# sheet1.net
KiCad netlist of a schematic drawn in Altium Designer
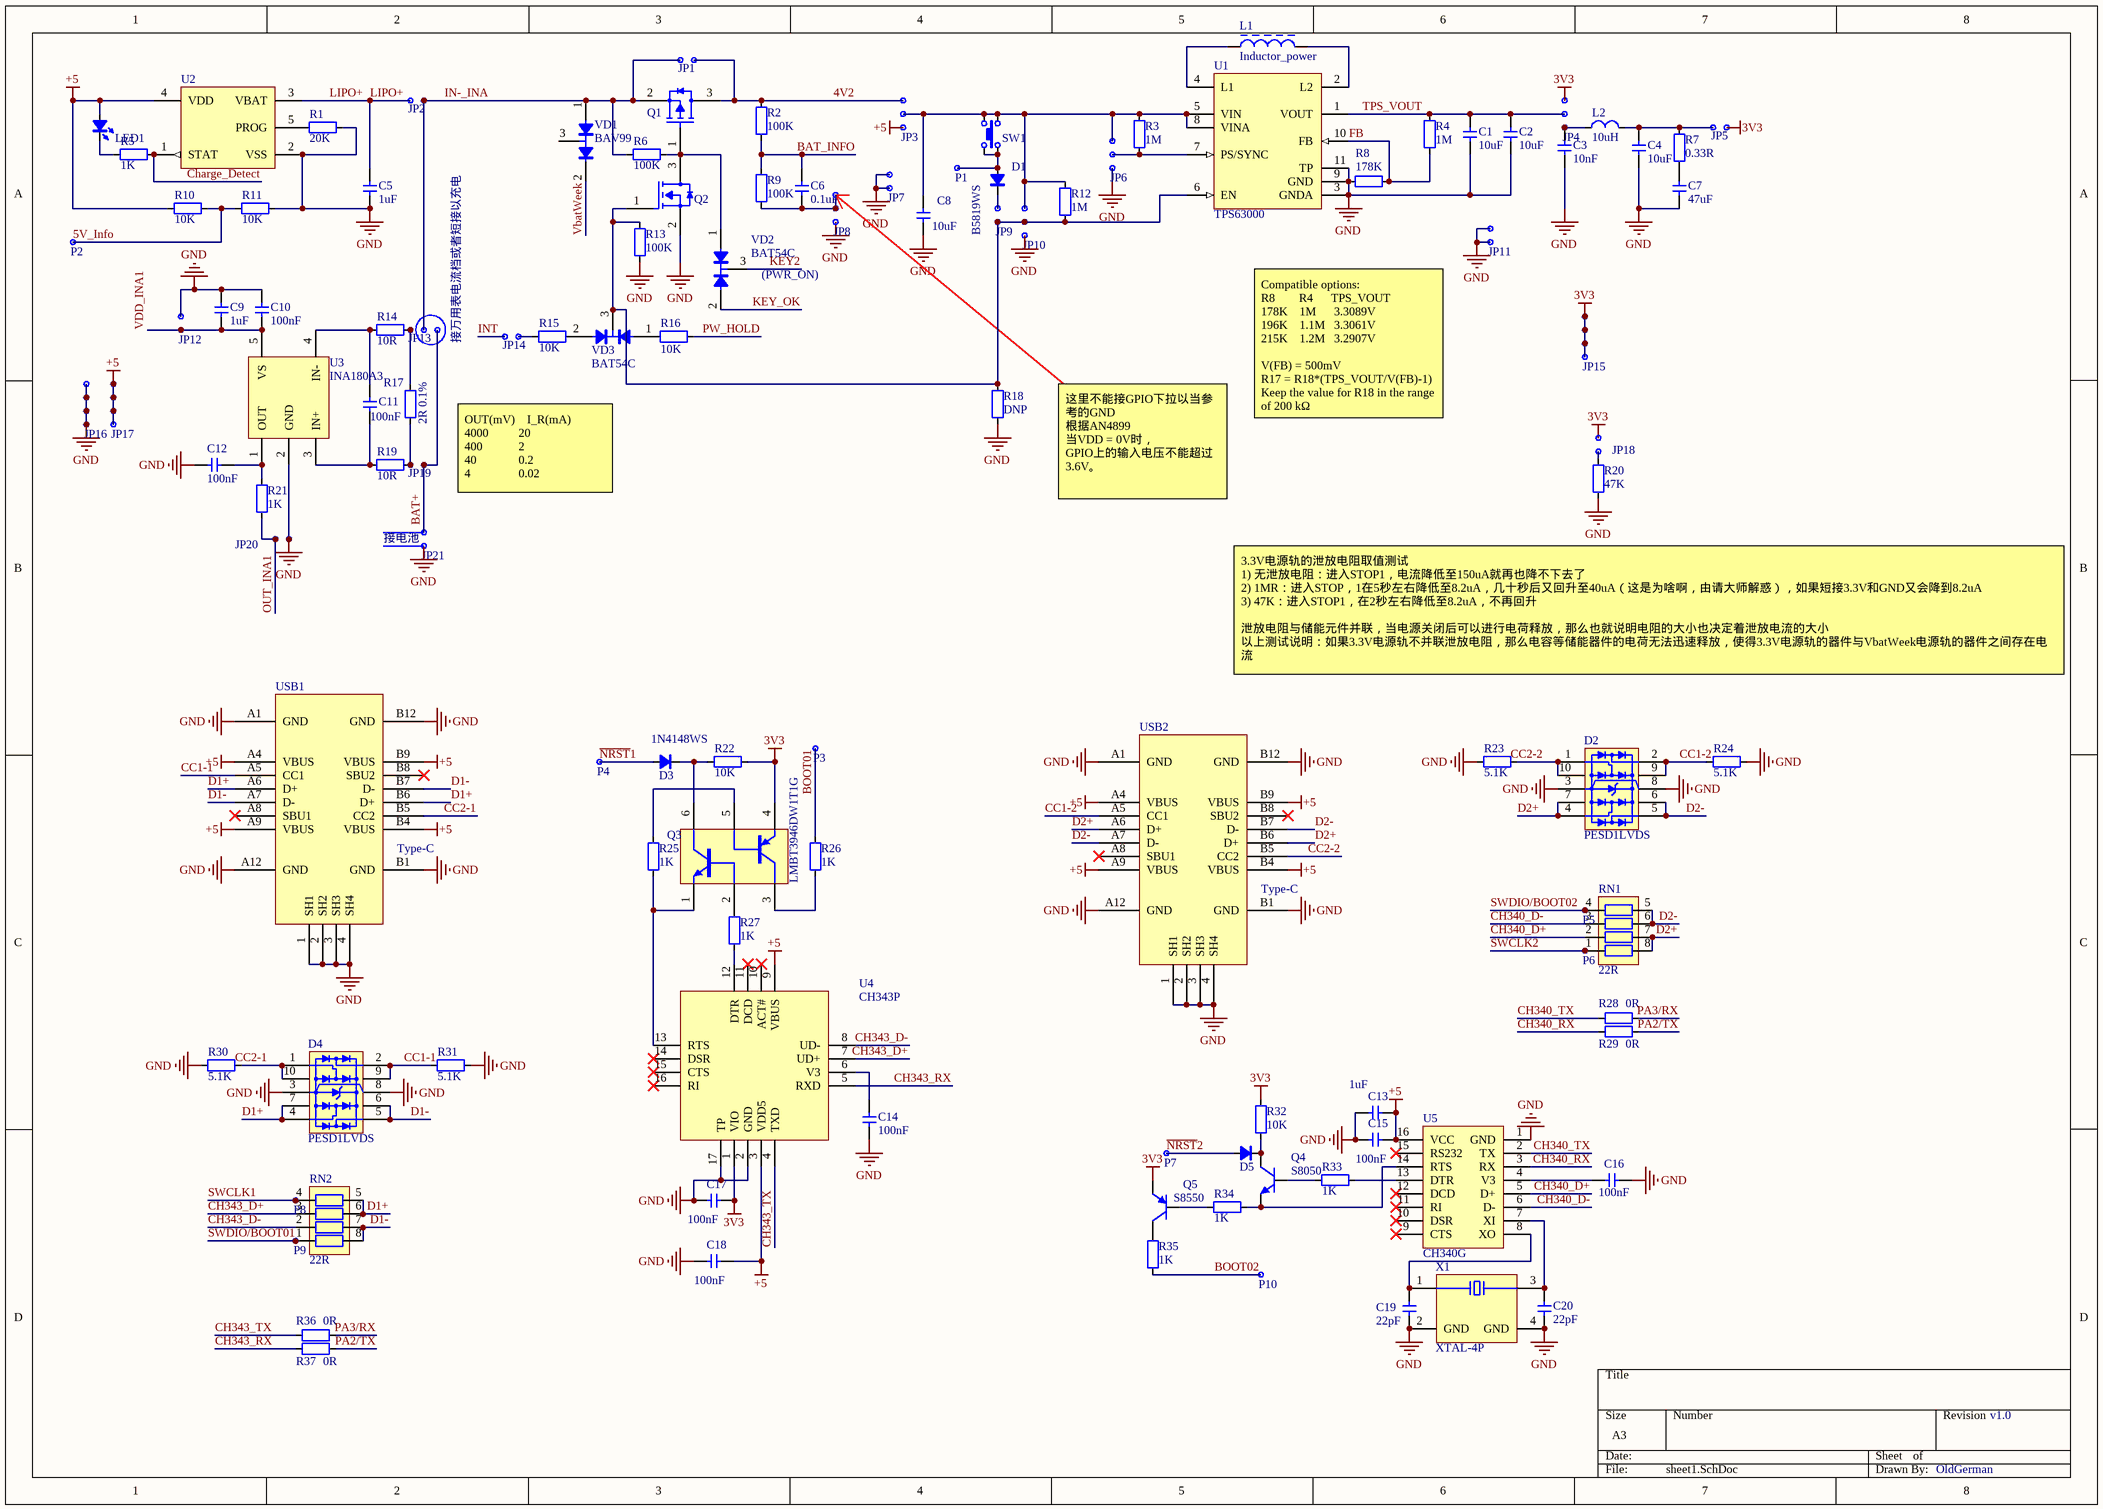
[diagram p0: sheet1.SchDoc]

(export (version "E")
  (design (tool "Eeschema 10.0.6"))
  (components
    (comp (ref "C1")
      (value "10uF")
      (footprint "C0603")
      (description "Capacitor")
      (libsource (lib "ODG_AD_Lib") (part "CAP"))
    )
    (comp (ref "C2")
      (value "10uF")
      (footprint "C0603")
      (description "Capacitor")
      (libsource (lib "ODG_AD_Lib") (part "CAP"))
    )
    (comp (ref "C3")
      (value "10nF")
      (footprint "C0603")
      (description "Capacitor")
      (libsource (lib "ODG_AD_Lib") (part "CAP"))
    )
    (comp (ref "C4")
      (value "10uF")
      (footprint "C0603")
      (description "Capacitor")
      (libsource (lib "ODG_AD_Lib") (part "CAP"))
    )
    (comp (ref "C5")
      (value "1uF")
      (footprint "C0603")
      (description "Capacitor")
      (libsource (lib "ODG_AD_Lib") (part "CAP"))
    )
    (comp (ref "C6")
      (value "0.1uF")
      (footprint "C0603")
      (description "Capacitor")
      (libsource (lib "ODG_AD_Lib") (part "CAP"))
    )
    (comp (ref "C7")
      (value "47uF")
      (footprint "C1206")
      (description "Capacitor")
      (libsource (lib "ODG_AD_Lib") (part "CAP"))
    )
    (comp (ref "C8")
      (value "10uF")
      (footprint "C0603")
      (description "Capacitor")
      (libsource (lib "ODG_AD_Lib") (part "CAP"))
    )
    (comp (ref "C9")
      (value "1uF")
      (footprint "C0603")
      (description "Capacitor")
      (libsource (lib "ODG_AD_Lib") (part "CAP"))
    )
    (comp (ref "C10")
      (value "100nF")
      (footprint "C0603")
      (description "Capacitor")
      (libsource (lib "ODG_AD_Lib") (part "CAP"))
    )
    (comp (ref "C11")
      (value "100nF")
      (footprint "C0603")
      (description "Capacitor")
      (libsource (lib "ODG_AD_Lib") (part "CAP"))
    )
    (comp (ref "C12")
      (value "100nF")
      (footprint "C0603")
      (description "Capacitor")
      (libsource (lib "ODG_AD_Lib") (part "CAP"))
    )
    (comp (ref "C13")
      (value "1uF")
      (footprint "C0603")
      (description "Capacitor")
      (libsource (lib "ODG_AD_Lib") (part "CAP"))
    )
    (comp (ref "C14")
      (value "100nF")
      (footprint "C0603")
      (description "Capacitor")
      (libsource (lib "ODG_AD_Lib") (part "CAP"))
    )
    (comp (ref "C15")
      (value "100nF")
      (footprint "C0603")
      (description "Capacitor")
      (libsource (lib "ODG_AD_Lib") (part "CAP"))
    )
    (comp (ref "C16")
      (value "100nF")
      (footprint "C0603")
      (description "Capacitor")
      (libsource (lib "ODG_AD_Lib") (part "CAP"))
    )
    (comp (ref "C17")
      (value "100nF")
      (footprint "C0603")
      (description "Capacitor")
      (libsource (lib "ODG_AD_Lib") (part "CAP"))
    )
    (comp (ref "C18")
      (value "100nF")
      (footprint "C0603")
      (description "Capacitor")
      (libsource (lib "ODG_AD_Lib") (part "CAP"))
    )
    (comp (ref "C19")
      (value "22pF")
      (footprint "C0603")
      (description "Capacitor")
      (libsource (lib "ODG_AD_Lib") (part "CAP"))
    )
    (comp (ref "C20")
      (value "22pF")
      (footprint "C0603")
      (description "Capacitor")
      (libsource (lib "ODG_AD_Lib") (part "CAP"))
    )
    (comp (ref "D1")
      (value "B5819WS")
      (footprint "SOD-323")
      (description "肖特基二极管")
      (libsource (lib "ODG_AD_Lib") (part "DIODE"))
    )
    (comp (ref "D2")
      (value "PESD1LVDS")
      (footprint "DFN2510-10_SOT1165-1")
      (description "Ultra-Low Capacitance TVS Protection")
      (fields (field (name "版权归属") "源创客"))
      (libsource (lib "ODG_AD_Lib") (part "PESD1LVDS"))
    )
    (comp (ref "D3")
      (value "1N4148WS")
      (footprint "SOD-323")
      (description "二极管")
      (libsource (lib "") (part "DIODE_1"))
    )
    (comp (ref "D4")
      (value "PESD1LVDS")
      (footprint "DFN2510-10_SOT1165-1")
      (description "Ultra-Low Capacitance TVS Protection")
      (fields (field (name "版权归属") "源创客"))
      (libsource (lib "ODG_AD_Lib") (part "PESD1LVDS"))
    )
    (comp (ref "D5")
      (value "DIODE")
      (footprint "SOD-323")
      (description "二极管")
      (libsource (lib "") (part "DIODE_1"))
    )
    (comp (ref "JP1")
      (value "CONN_X2_DOT")
      (footprint "2.54mm_Male_x2")
      (libsource (lib "ODG_Project") (part "CONN_X2_DOT"))
    )
    (comp (ref "JP2")
      (value "CONN_X2_DOT")
      (footprint "2.54mm_Male_x2")
      (libsource (lib "ODG_AD_Lib") (part "CONN_X2_DOT"))
    )
    (comp (ref "JP3")
      (value "CONN_X3_DOT")
      (footprint "2.54mm_Male_x3")
      (libsource (lib "ODG_Project") (part "CONN_X3_DOT"))
    )
    (comp (ref "JP4")
      (value "CONN_X3_DOT")
      (footprint "2.54mm_Male_x3")
      (libsource (lib "ODG_Project") (part "CONN_X3_DOT"))
    )
    (comp (ref "JP5")
      (value "CONN_X2_DOT")
      (footprint "2.54mm_Male_x2")
      (libsource (lib "ODG_Project") (part "CONN_X2_DOT"))
    )
    (comp (ref "JP6")
      (value "CONN_X3_DOT")
      (footprint "2.54mm_Male_x3")
      (libsource (lib "ODG_Project") (part "CONN_X3_DOT"))
    )
    (comp (ref "JP7")
      (value "CONN_X2_DOT")
      (footprint "2.54mm_Male_x2")
      (libsource (lib "ODG_Project") (part "CONN_X2_DOT"))
    )
    (comp (ref "JP8")
      (value "CONN_X3_DOT")
      (footprint "2.54mm_Male_x3")
      (libsource (lib "ODG_Project") (part "CONN_X3_DOT"))
    )
    (comp (ref "JP9")
      (value "CONN_X2_DOT")
      (footprint "2.54mm_Male_x2")
      (libsource (lib "ODG_Project") (part "CONN_X2_DOT"))
    )
    (comp (ref "JP10")
      (value "CONN_X3_DOT")
      (footprint "2.54mm_Male_x3")
      (libsource (lib "ODG_Project") (part "CONN_X3_DOT"))
    )
    (comp (ref "JP11")
      (value "CONN_X2_DOT")
      (footprint "2.54mm_Male_x2")
      (libsource (lib "ODG_Project") (part "CONN_X2_DOT"))
    )
    (comp (ref "JP12")
      (value "CONN_X2_DOT")
      (footprint "2.54mm_Male_x2")
      (libsource (lib "ODG_AD_Lib") (part "CONN_X2_DOT"))
    )
    (comp (ref "JP13")
      (value "CONN_X3_DOT")
      (footprint "2.54mm_Male_x3")
      (libsource (lib "ODG_AD_Lib") (part "CONN_X3_DOT"))
    )
    (comp (ref "JP14")
      (value "CONN_X2_DOT")
      (footprint "2.54mm_Male_x2")
      (libsource (lib "ODG_AD_Lib") (part "CONN_X2_DOT"))
    )
    (comp (ref "JP15")
      (value "CONN_X4_DOT")
      (footprint "2.54mm_Male_x4")
      (libsource (lib "ODG_AD_Lib") (part "CONN_X4_DOT"))
    )
    (comp (ref "JP16")
      (value "CONN_X4_DOT")
      (footprint "2.54mm_Male_x4")
      (libsource (lib "ODG_AD_Lib") (part "CONN_X4_DOT"))
    )
    (comp (ref "JP17")
      (value "CONN_X4_DOT")
      (footprint "2.54mm_Male_x4")
      (libsource (lib "ODG_AD_Lib") (part "CONN_X4_DOT"))
    )
    (comp (ref "JP18")
      (value "CONN_X2_DOT")
      (footprint "2.54mm_Male_x2")
      (libsource (lib "ODG_Project") (part "CONN_X2_DOT"))
    )
    (comp (ref "JP19")
      (value "CONN_X2_DOT")
      (footprint "2.54mm_Male_x2")
      (libsource (lib "ODG_AD_Lib") (part "CONN_X2_DOT"))
    )
    (comp (ref "JP20")
      (value "CONN_X2_DOT")
      (footprint "2.54mm_Male_x2")
      (libsource (lib "ODG_AD_Lib") (part "CONN_X2_DOT"))
    )
    (comp (ref "JP21")
      (value "CONN_X2_DOT")
      (footprint "2.54mm_Male_x2")
      (libsource (lib "ODG_AD_Lib") (part "CONN_X2_DOT"))
    )
    (comp (ref "L1")
      (value "Inductor_power")
      (footprint "TDK VLS252012CX")
      (description "功率电感")
      (libsource (lib "ODG_Project") (part "Inductor_power"))
    )
    (comp (ref "L2")
      (value "10uH")
      (footprint "FER0805")
      (description "贴片叠层电感")
      (libsource (lib "ODG_AD_Lib") (part "inductor_mini"))
    )
    (comp (ref "LED1") (value "LED") (footprint "LED0603_WHITE") (libsource (lib "ODG_AD_Lib") (part "LED")))
    (comp (ref "P1")
      (value "CONN_X1_DOT")
      (footprint "2.54mm_Male_x1")
      (libsource (lib "ODG_AD_Lib") (part "CONN_X1_DOT"))
    )
    (comp (ref "P2")
      (value "CONN_X1_DOT")
      (footprint "2.54mm_Male_x1")
      (libsource (lib "ODG_AD_Lib") (part "CONN_X1_DOT"))
    )
    (comp (ref "P3")
      (value "CONN_X1_DOT")
      (footprint "2.54mm_Male_x1")
      (libsource (lib "ODG_AD_Lib") (part "CONN_X1_DOT"))
    )
    (comp (ref "P4")
      (value "CONN_X1_DOT")
      (footprint "2.54mm_Male_x1")
      (libsource (lib "ODG_AD_Lib") (part "CONN_X1_DOT"))
    )
    (comp (ref "P5")
      (value "CONN_X1_DOT")
      (footprint "2.54mm_Male_x1")
      (libsource (lib "ODG_AD_Lib") (part "CONN_X1_DOT"))
    )
    (comp (ref "P6")
      (value "CONN_X1_DOT")
      (footprint "2.54mm_Male_x1")
      (libsource (lib "ODG_AD_Lib") (part "CONN_X1_DOT"))
    )
    (comp (ref "P7")
      (value "CONN_X1_DOT")
      (footprint "2.54mm_Male_x1")
      (libsource (lib "ODG_AD_Lib") (part "CONN_X1_DOT"))
    )
    (comp (ref "P8")
      (value "CONN_X1_DOT")
      (footprint "2.54mm_Male_x1")
      (libsource (lib "ODG_AD_Lib") (part "CONN_X1_DOT"))
    )
    (comp (ref "P9")
      (value "CONN_X1_DOT")
      (footprint "2.54mm_Male_x1")
      (libsource (lib "ODG_AD_Lib") (part "CONN_X1_DOT"))
    )
    (comp (ref "P10")
      (value "CONN_X1_DOT")
      (footprint "2.54mm_Male_x1")
      (libsource (lib "ODG_AD_Lib") (part "CONN_X1_DOT"))
    )
    (comp (ref "Q1")
      (value "P-MOS")
      (footprint "INFINEON SOT-23-3")
      (libsource (lib "ODG_AD_Lib") (part "P-MOS_123"))
    )
    (comp (ref "Q2")
      (value "N-MOS")
      (footprint "INFINEON SOT-23-3")
      (libsource (lib "ODG_AD_Lib") (part "N-MOS_123"))
    )
    (comp (ref "Q3")
      (value "LMBT3946DW1T1G")
      (footprint "ON SEMI SOT-363")
      (description "PNP+NPN, SOT-363")
      (libsource (lib "ODG_AD_Lib") (part "LMBT3946DW1T1G"))
    )
    (comp (ref "Q4")
      (value "S8050")
      (footprint "INFINEON SOT-23-3")
      (description "NPN型")
      (fields (field (name "版权归属") "源创客"))
      (libsource (lib "ODG_Project") (part "S8050"))
    )
    (comp (ref "Q5")
      (value "S8550")
      (footprint "INFINEON SOT-23-3")
      (description "PNP型")
      (fields (field (name "版权归属") "源创客"))
      (libsource (lib "ODG_AD_Lib") (part "S8550"))
    )
    (comp (ref "R1")
      (value "20K")
      (footprint "R0603")
      (description "Resistor")
      (libsource (lib "ODG_AD_Lib") (part "RES"))
    )
    (comp (ref "R2")
      (value "100K")
      (footprint "R0603")
      (description "Resistor")
      (libsource (lib "") (part "RES_1"))
    )
    (comp (ref "R3")
      (value "1M")
      (footprint "R0603")
      (description "Resistor")
      (libsource (lib "") (part "RES_2"))
    )
    (comp (ref "R4")
      (value "1M")
      (footprint "R0603")
      (description "Resistor")
      (libsource (lib "") (part "RES_1"))
    )
    (comp (ref "R5")
      (value "1K")
      (footprint "R0603")
      (description "Resistor")
      (libsource (lib "ODG_AD_Lib") (part "RES"))
    )
    (comp (ref "R6")
      (value "100K")
      (footprint "R0603")
      (description "Resistor")
      (libsource (lib "ODG_AD_Lib") (part "RES"))
    )
    (comp (ref "R7")
      (value "0.33R")
      (footprint "R0603")
      (description "Resistor")
      (libsource (lib "") (part "RES_1"))
    )
    (comp (ref "R8")
      (value "178K")
      (footprint "R0603")
      (description "Resistor")
      (libsource (lib "ODG_AD_Lib") (part "RES"))
    )
    (comp (ref "R9")
      (value "100K")
      (footprint "R0603")
      (description "Resistor")
      (libsource (lib "") (part "RES_1"))
    )
    (comp (ref "R10")
      (value "10K")
      (footprint "R0603")
      (description "Resistor")
      (libsource (lib "ODG_AD_Lib") (part "RES"))
    )
    (comp (ref "R11")
      (value "10K")
      (footprint "R0603")
      (description "Resistor")
      (libsource (lib "ODG_AD_Lib") (part "RES"))
    )
    (comp (ref "R12")
      (value "1M")
      (footprint "R0603")
      (description "Resistor")
      (libsource (lib "") (part "RES_2"))
    )
    (comp (ref "R13")
      (value "100K")
      (footprint "R0603")
      (description "Resistor")
      (libsource (lib "") (part "RES_1"))
    )
    (comp (ref "R14")
      (value "10R")
      (footprint "R0603")
      (description "Resistor")
      (libsource (lib "") (part "RES_3"))
    )
    (comp (ref "R15")
      (value "10K")
      (footprint "R0603")
      (description "Resistor")
      (libsource (lib "") (part "RES_3"))
    )
    (comp (ref "R16")
      (value "10K")
      (footprint "R0603")
      (description "Resistor")
      (libsource (lib "ODG_AD_Lib") (part "RES"))
    )
    (comp (ref "R17")
      (value "2R 0.1%")
      (footprint "R0805")
      (description "Resistor")
      (libsource (lib "") (part "RES_2"))
    )
    (comp (ref "R18")
      (value "DNP")
      (footprint "R0603")
      (description "Resistor")
      (libsource (lib "") (part "RES_1"))
    )
    (comp (ref "R19")
      (value "10R")
      (footprint "R0603")
      (description "Resistor")
      (libsource (lib "") (part "RES_3"))
    )
    (comp (ref "R20")
      (value "47K")
      (footprint "R0603")
      (description "Resistor")
      (libsource (lib "") (part "RES_1"))
    )
    (comp (ref "R21")
      (value "1K")
      (footprint "R0603")
      (description "Resistor")
      (libsource (lib "") (part "RES_1"))
    )
    (comp (ref "R22")
      (value "10K")
      (footprint "R0603")
      (description "Resistor")
      (libsource (lib "ODG_AD_Lib") (part "RES"))
    )
    (comp (ref "R23")
      (value "5.1K")
      (footprint "R0603")
      (description "Resistor")
      (libsource (lib "ODG_AD_Lib") (part "RES"))
    )
    (comp (ref "R24")
      (value "5.1K")
      (footprint "R0603")
      (description "Resistor")
      (libsource (lib "") (part "RES_2"))
    )
    (comp (ref "R25")
      (value "1K")
      (footprint "R0603")
      (description "Resistor")
      (libsource (lib "") (part "RES_2"))
    )
    (comp (ref "R26")
      (value "1K")
      (footprint "R0603")
      (description "Resistor")
      (libsource (lib "") (part "RES_2"))
    )
    (comp (ref "R27")
      (value "1K")
      (footprint "R0603")
      (description "Resistor")
      (libsource (lib "") (part "RES_1"))
    )
    (comp (ref "R28")
      (value "0R")
      (footprint "R0603")
      (description "Resistor")
      (libsource (lib "") (part "RES_3"))
    )
    (comp (ref "R29")
      (value "0R")
      (footprint "R0603")
      (description "Resistor")
      (libsource (lib "") (part "RES_3"))
    )
    (comp (ref "R30")
      (value "5.1K")
      (footprint "R0603")
      (description "Resistor")
      (libsource (lib "ODG_AD_Lib") (part "RES"))
    )
    (comp (ref "R31")
      (value "5.1K")
      (footprint "R0603")
      (description "Resistor")
      (libsource (lib "") (part "RES_2"))
    )
    (comp (ref "R32")
      (value "10K")
      (footprint "R0603")
      (description "Resistor")
      (libsource (lib "") (part "RES_2"))
    )
    (comp (ref "R33")
      (value "1K")
      (footprint "R0603")
      (description "Resistor")
      (libsource (lib "") (part "RES_3"))
    )
    (comp (ref "R34")
      (value "1K")
      (footprint "R0603")
      (description "Resistor")
      (libsource (lib "") (part "RES_3"))
    )
    (comp (ref "R35")
      (value "1K")
      (footprint "R0603")
      (description "Resistor")
      (libsource (lib "") (part "RES_2"))
    )
    (comp (ref "R36")
      (value "0R")
      (footprint "R0603")
      (description "Resistor")
      (libsource (lib "") (part "RES_3"))
    )
    (comp (ref "R37")
      (value "0R")
      (footprint "R0603")
      (description "Resistor")
      (libsource (lib "") (part "RES_3"))
    )
    (comp (ref "RN1")
      (value "22R")
      (footprint "RESNET 1206-8 CONCAVE")
      (description "贴片网络排阻")
      (fields (field (name "版权归属") "源创客"))
      (libsource (lib "ODG_AD_Lib") (part "RES-8P4R"))
    )
    (comp (ref "RN2")
      (value "22R")
      (footprint "RESNET 1206-8 CONCAVE")
      (description "贴片网络排阻")
      (fields (field (name "版权归属") "源创客"))
      (libsource (lib "ODG_AD_Lib") (part "RES-8P4R"))
    )
    (comp (ref "SW1")
      (value "Button-4P")
      (footprint "SWITCH_3X4X2.5_4PIN_SMD")
      (description "Button")
      (libsource (lib "ODG_AD_Lib") (part "Button-4P"))
    )
    (comp (ref "U1")
      (value "TPS63000")
      (footprint "TI PVSON-10 3x3MM DRC")
      (description "Buck-Boost Converter\r\n具有 1.8A 电流开关并采用 3x3 QFN 封装的高效率降压/升压转换器")
      (libsource (lib "ODG_AD_Lib") (part "TPS63000"))
    )
    (comp (ref "U2")
      (value "MCP73831T")
      (footprint "MICROCHIP SOT-23-5 OT")
      (libsource (lib "ODG_AD_Lib") (part "MCP73831T"))
    )
    (comp (ref "U3")
      (value "INA180A3")
      (footprint "TI SOT-23-5 DBV")
      (description "Low- and High-Side Voltage Output, Current-Sense Amplifiers")
      (libsource (lib "ODG_AD_Lib") (part "INA180Ax"))
    )
    (comp (ref "U4")
      (value "CH343P")
      (footprint "Analog QFN-16 3x3MM")
      (description "usb to ttl")
      (libsource (lib "ODG_Project") (part "CH343P"))
    )
    (comp (ref "U5")
      (value "CH340G")
      (footprint "TI SOP-16 D")
      (description "丐中丐，需要外接12M晶振")
      (libsource (lib "ODG_AD_Lib") (part "CH340G"))
    )
    (comp (ref "USB1")
      (value "Type-C")
      (footprint "Type-C-TOP")
      (libsource (lib "ODG_AD_Lib") (part "USB-Type-C_16P"))
    )
    (comp (ref "USB2")
      (value "Type-C")
      (footprint "Type-C-TOP")
      (libsource (lib "ODG_AD_Lib") (part "USB-Type-C_16P"))
    )
    (comp (ref "VD1")
      (value "BAV99")
      (footprint "INFINEON SOT-23-3")
      (description "Dual Series Switching Diodes")
      (fields (field (name "版权归属") "源创客"))
      (libsource (lib "ODG_AD_Lib") (part "BAV99"))
    )
    (comp (ref "VD2")
      (value "BAT54C")
      (footprint "INFINEON SOT-23-3")
      (description "贴片肖特基二极管")
      (fields (field (name "版权归属") "源创客"))
      (libsource (lib "ODG_AD_Lib") (part "BAT54C"))
    )
    (comp (ref "VD3")
      (value "BAT54C")
      (footprint "INFINEON SOT-23-3")
      (description "贴片肖特基二极管")
      (fields (field (name "版权归属") "源创客"))
      (libsource (lib "ODG_AD_Lib") (part "BAT54C"))
    )
    (comp (ref "X1")
      (value "XTAL-4P")
      (footprint "EPSON TSX-3225")
      (description "4脚无源石英晶振")
      (fields (field (name "版权归属") "源创客"))
      (libsource (lib "ODG_AD_Lib") (part "XTAL-4P"))
    )
  )
  (nets
    (net (code "1") (name "+5") (class "Default")
      (node (ref "C13") (pin "2") (pinfunction "2_2") (pintype "passive"))
      (node (ref "C15") (pin "2") (pinfunction "2_2") (pintype "passive"))
      (node (ref "C18") (pin "2") (pinfunction "2_2") (pintype "passive"))
      (node (ref "JP17") (pin "1") (pinfunction "1_1") (pintype "passive"))
      (node (ref "JP17") (pin "2") (pinfunction "2_2") (pintype "passive"))
      (node (ref "JP17") (pin "3") (pinfunction "3_3") (pintype "passive"))
      (node (ref "JP17") (pin "4") (pinfunction "4_4") (pintype "passive"))
      (node (ref "JP3") (pin "3") (pinfunction "3_3") (pintype "passive"))
      (node (ref "LED1") (pin "1") (pinfunction "A_1") (pintype "passive"))
      (node (ref "R10") (pin "2") (pinfunction "2_2") (pintype "passive"))
      (node (ref "U2") (pin "4") (pinfunction "VDD_4") (pintype "power_in"))
      (node (ref "U4") (pin "3") (pinfunction "VDD5_3") (pintype "passive"))
      (node (ref "U4") (pin "9") (pinfunction "VBUS_9") (pintype "passive"))
      (node (ref "U5") (pin "16") (pinfunction "VCC_16") (pintype "passive"))
      (node (ref "USB1") (pin "A4") (pinfunction "VBUS_A4") (pintype "passive"))
      (node (ref "USB1") (pin "A9") (pinfunction "VBUS_A9") (pintype "passive"))
      (node (ref "USB1") (pin "B4") (pinfunction "VBUS_B4") (pintype "passive"))
      (node (ref "USB1") (pin "B9") (pinfunction "VBUS_B9") (pintype "passive"))
      (node (ref "USB2") (pin "A4") (pinfunction "VBUS_A4") (pintype "passive"))
      (node (ref "USB2") (pin "A9") (pinfunction "VBUS_A9") (pintype "passive"))
      (node (ref "USB2") (pin "B4") (pinfunction "VBUS_B4") (pintype "passive"))
      (node (ref "USB2") (pin "B9") (pinfunction "VBUS_B9") (pintype "passive"))
    )
    (net (code "2") (name "/4V2") (class "Default")
      (node (ref "JP1") (pin "2") (pinfunction "2_2") (pintype "passive"))
      (node (ref "JP3") (pin "1") (pinfunction "1_1") (pintype "passive"))
      (node (ref "Q1") (pin "3") (pinfunction "D_3") (pintype "passive"))
      (node (ref "R2") (pin "2") (pinfunction "2_2") (pintype "passive"))
    )
    (net (code "3") (name "/5V_Info") (class "Default")
      (node (ref "P2") (pin "1") (pinfunction "1_1") (pintype "passive"))
      (node (ref "R10") (pin "1") (pinfunction "1_1") (pintype "passive"))
      (node (ref "R11") (pin "2") (pinfunction "2_2") (pintype "passive"))
    )
    (net (code "4") (name "/BAT+") (class "Default")
      (node (ref "JP13") (pin "3") (pinfunction "3_3") (pintype "passive"))
      (node (ref "JP19") (pin "2") (pinfunction "2_2") (pintype "passive"))
      (node (ref "JP21") (pin "1") (pinfunction "1_1") (pintype "passive"))
    )
    (net (code "5") (name "/BAT_INFO") (class "Default")
      (node (ref "C6") (pin "1") (pinfunction "1_1") (pintype "passive"))
      (node (ref "R2") (pin "1") (pinfunction "1_1") (pintype "passive"))
      (node (ref "R9") (pin "2") (pinfunction "2_2") (pintype "passive"))
    )
    (net (code "6") (name "/BOOT01") (class "Default")
      (node (ref "P3") (pin "1") (pinfunction "1_1") (pintype "passive"))
      (node (ref "R26") (pin "1") (pinfunction "1_1") (pintype "passive"))
    )
    (net (code "7") (name "/BOOT02") (class "Default")
      (node (ref "P10") (pin "1") (pinfunction "1_1") (pintype "passive"))
      (node (ref "R35") (pin "2") (pinfunction "2_2") (pintype "passive"))
    )
    (net (code "8") (name "/CC1-1") (class "Default")
      (node (ref "D4") (pin "2") (pinfunction "I/O_2") (pintype "passive"))
      (node (ref "D4") (pin "9") (pinfunction "GND_9") (pintype "passive"))
      (node (ref "R31") (pin "2") (pinfunction "2_2") (pintype "passive"))
      (node (ref "USB1") (pin "A5") (pinfunction "CC1_A5") (pintype "passive"))
    )
    (net (code "9") (name "/CC1-2") (class "Default")
      (node (ref "D2") (pin "2") (pinfunction "I/O_2") (pintype "passive"))
      (node (ref "D2") (pin "9") (pinfunction "GND_9") (pintype "passive"))
      (node (ref "R24") (pin "2") (pinfunction "2_2") (pintype "passive"))
      (node (ref "USB2") (pin "A5") (pinfunction "CC1_A5") (pintype "passive"))
    )
    (net (code "10") (name "/CC2-1") (class "Default")
      (node (ref "D4") (pin "1") (pinfunction "I/O_1") (pintype "passive"))
      (node (ref "D4") (pin "10") (pinfunction "GND_10") (pintype "passive"))
      (node (ref "R30") (pin "1") (pinfunction "1_1") (pintype "passive"))
      (node (ref "USB1") (pin "B5") (pinfunction "CC2_B5") (pintype "passive"))
    )
    (net (code "11") (name "/CC2-2") (class "Default")
      (node (ref "D2") (pin "1") (pinfunction "I/O_1") (pintype "passive"))
      (node (ref "D2") (pin "10") (pinfunction "GND_10") (pintype "passive"))
      (node (ref "R23") (pin "1") (pinfunction "1_1") (pintype "passive"))
      (node (ref "USB2") (pin "B5") (pinfunction "CC2_B5") (pintype "passive"))
    )
    (net (code "12") (name "/CH340_D+") (class "Default")
      (node (ref "RN1") (pin "2") (pinfunction "2_2") (pintype "passive"))
      (node (ref "U5") (pin "5") (pinfunction "D+_5") (pintype "passive"))
    )
    (net (code "13") (name "/CH340_D-") (class "Default")
      (node (ref "RN1") (pin "3") (pinfunction "3_3") (pintype "passive"))
      (node (ref "U5") (pin "6") (pinfunction "D-_6") (pintype "passive"))
    )
    (net (code "14") (name "/CH340_RX") (class "Default")
      (node (ref "R29") (pin "1") (pinfunction "1_1") (pintype "passive"))
      (node (ref "U5") (pin "3") (pinfunction "RX_3") (pintype "passive"))
    )
    (net (code "15") (name "/CH340_TX") (class "Default")
      (node (ref "R28") (pin "1") (pinfunction "1_1") (pintype "passive"))
      (node (ref "U5") (pin "2") (pinfunction "TX_2") (pintype "passive"))
    )
    (net (code "16") (name "/CH343_D+") (class "Default")
      (node (ref "RN2") (pin "3") (pinfunction "3_3") (pintype "passive"))
      (node (ref "U4") (pin "7") (pinfunction "UD+_7") (pintype "passive"))
    )
    (net (code "17") (name "/CH343_D-") (class "Default")
      (node (ref "RN2") (pin "2") (pinfunction "2_2") (pintype "passive"))
      (node (ref "U4") (pin "8") (pinfunction "UD-_8") (pintype "passive"))
    )
    (net (code "18") (name "/CH343_RX") (class "Default")
      (node (ref "R37") (pin "1") (pinfunction "1_1") (pintype "passive"))
      (node (ref "U4") (pin "5") (pinfunction "RXD_5") (pintype "passive"))
    )
    (net (code "19") (name "/CH343_TX") (class "Default")
      (node (ref "R36") (pin "1") (pinfunction "1_1") (pintype "passive"))
      (node (ref "U4") (pin "4") (pinfunction "TXD_4") (pintype "passive"))
    )
    (net (code "20") (name "/Charge_Detect") (class "Default")
      (node (ref "R5") (pin "1") (pinfunction "1_1") (pintype "passive"))
      (node (ref "U2") (pin "1") (pinfunction "STAT_1") (pintype "output"))
    )
    (net (code "21") (name "/D1+") (class "Default")
      (node (ref "D4") (pin "4") (pinfunction "I/O_4") (pintype "passive"))
      (node (ref "D4") (pin "7") (pinfunction "GND_7") (pintype "passive"))
      (node (ref "RN2") (pin "5") (pinfunction "5_5") (pintype "passive"))
      (node (ref "RN2") (pin "6") (pinfunction "6_6") (pintype "passive"))
      (node (ref "USB1") (pin "A6") (pinfunction "D+_A6") (pintype "passive"))
      (node (ref "USB1") (pin "B6") (pinfunction "D+_B6") (pintype "passive"))
    )
    (net (code "22") (name "/D1-") (class "Default")
      (node (ref "D4") (pin "5") (pinfunction "I/O_5") (pintype "passive"))
      (node (ref "D4") (pin "6") (pinfunction "GND_6") (pintype "passive"))
      (node (ref "RN2") (pin "7") (pinfunction "7_7") (pintype "passive"))
      (node (ref "RN2") (pin "8") (pinfunction "8_8") (pintype "passive"))
      (node (ref "USB1") (pin "A7") (pinfunction "D-_A7") (pintype "passive"))
      (node (ref "USB1") (pin "B7") (pinfunction "D-_B7") (pintype "passive"))
    )
    (net (code "23") (name "/D2+") (class "Default")
      (node (ref "D2") (pin "4") (pinfunction "I/O_4") (pintype "passive"))
      (node (ref "D2") (pin "7") (pinfunction "GND_7") (pintype "passive"))
      (node (ref "RN1") (pin "7") (pinfunction "7_7") (pintype "passive"))
      (node (ref "RN1") (pin "8") (pinfunction "8_8") (pintype "passive"))
      (node (ref "USB2") (pin "A6") (pinfunction "D+_A6") (pintype "passive"))
      (node (ref "USB2") (pin "B6") (pinfunction "D+_B6") (pintype "passive"))
    )
    (net (code "24") (name "/D2-") (class "Default")
      (node (ref "D2") (pin "5") (pinfunction "I/O_5") (pintype "passive"))
      (node (ref "D2") (pin "6") (pinfunction "GND_6") (pintype "passive"))
      (node (ref "RN1") (pin "5") (pinfunction "5_5") (pintype "passive"))
      (node (ref "RN1") (pin "6") (pinfunction "6_6") (pintype "passive"))
      (node (ref "USB2") (pin "A7") (pinfunction "D-_A7") (pintype "passive"))
      (node (ref "USB2") (pin "B7") (pinfunction "D-_B7") (pintype "passive"))
    )
    (net (code "25") (name "/FB") (class "Default")
      (node (ref "R4") (pin "1") (pinfunction "1_1") (pintype "passive"))
      (node (ref "R8") (pin "1") (pinfunction "1_1") (pintype "passive"))
      (node (ref "U1") (pin "10") (pinfunction "FB_10") (pintype "input"))
    )
    (net (code "26") (name "/IN-_INA") (class "Default")
      (node (ref "JP1") (pin "1") (pinfunction "1_1") (pintype "passive"))
      (node (ref "JP13") (pin "2") (pinfunction "2_2") (pintype "passive"))
      (node (ref "JP2") (pin "2") (pinfunction "2_2") (pintype "passive"))
      (node (ref "Q1") (pin "2") (pinfunction "S_2") (pintype "passive"))
      (node (ref "R6") (pin "2") (pinfunction "2_2") (pintype "passive"))
      (node (ref "VD1") (pin "1") (pinfunction "1_1") (pintype "passive"))
    )
    (net (code "27") (name "/INT") (class "Default")
      (node (ref "JP14") (pin "1") (pinfunction "1_1") (pintype "passive"))
    )
    (net (code "28") (name "/KEY2") (class "Default")
      (node (ref "VD2") (pin "3") (pinfunction "3_3") (pintype "passive"))
    )
    (net (code "29") (name "/KEY_OK") (class "Default")
      (node (ref "VD2") (pin "2") (pinfunction "2_2") (pintype "passive"))
    )
    (net (code "30") (name "/LIPO+") (class "Default")
      (node (ref "C5") (pin "1") (pinfunction "1_1") (pintype "passive"))
      (node (ref "JP2") (pin "1") (pinfunction "1_1") (pintype "passive"))
      (node (ref "U2") (pin "3") (pinfunction "VBAT_3") (pintype "power_in"))
    )
    (net (code "31") (name "/OUT_INA1") (class "Default")
      (node (ref "JP20") (pin "1") (pinfunction "1_1") (pintype "passive"))
      (node (ref "R21") (pin "1") (pinfunction "1_1") (pintype "passive"))
    )
    (net (code "32") (name "/PA2{slash}TX") (class "Default")
      (node (ref "R29") (pin "2") (pinfunction "2_2") (pintype "passive"))
      (node (ref "R37") (pin "2") (pinfunction "2_2") (pintype "passive"))
    )
    (net (code "33") (name "/PA3{slash}RX") (class "Default")
      (node (ref "R28") (pin "2") (pinfunction "2_2") (pintype "passive"))
      (node (ref "R36") (pin "2") (pinfunction "2_2") (pintype "passive"))
    )
    (net (code "34") (name "/PW_HOLD") (class "Default")
      (node (ref "R16") (pin "1") (pinfunction "1_1") (pintype "passive"))
    )
    (net (code "35") (name "/SWCLK1") (class "Default")
      (node (ref "P8") (pin "1") (pinfunction "1_1") (pintype "passive"))
      (node (ref "RN2") (pin "4") (pinfunction "4_4") (pintype "passive"))
    )
    (net (code "36") (name "/SWCLK2") (class "Default")
      (node (ref "P6") (pin "1") (pinfunction "1_1") (pintype "passive"))
      (node (ref "RN1") (pin "1") (pinfunction "1_1") (pintype "passive"))
    )
    (net (code "37") (name "/SWDIO{slash}BOOT01") (class "Default")
      (node (ref "P9") (pin "1") (pinfunction "1_1") (pintype "passive"))
      (node (ref "RN2") (pin "1") (pinfunction "1_1") (pintype "passive"))
    )
    (net (code "38") (name "/SWDIO{slash}BOOT02") (class "Default")
      (node (ref "P5") (pin "1") (pinfunction "1_1") (pintype "passive"))
      (node (ref "RN1") (pin "4") (pinfunction "4_4") (pintype "passive"))
    )
    (net (code "39") (name "/TPS_VOUT") (class "Default")
      (node (ref "C1") (pin "1") (pinfunction "1_1") (pintype "passive"))
      (node (ref "C2") (pin "1") (pinfunction "1_1") (pintype "passive"))
      (node (ref "JP4") (pin "2") (pinfunction "2_2") (pintype "passive"))
      (node (ref "R4") (pin "2") (pinfunction "2_2") (pintype "passive"))
      (node (ref "U1") (pin "1") (pinfunction "VOUT_1") (pintype "passive"))
    )
    (net (code "40") (name "/VDD_INA1") (class "Default")
      (node (ref "C10") (pin "1") (pinfunction "1_1") (pintype "passive"))
      (node (ref "C9") (pin "1") (pinfunction "1_1") (pintype "passive"))
      (node (ref "JP12") (pin "2") (pinfunction "2_2") (pintype "passive"))
      (node (ref "U3") (pin "5") (pinfunction "VS_5") (pintype "passive"))
    )
    (net (code "41") (name "/VbatWeek") (class "Default")
      (node (ref "VD1") (pin "2") (pinfunction "2_2") (pintype "passive"))
    )
    (net (code "42") (name "/~{NRST}1") (class "Default")
      (node (ref "D3") (pin "1") (pinfunction "A_1") (pintype "passive"))
      (node (ref "P4") (pin "1") (pinfunction "1_1") (pintype "passive"))
    )
    (net (code "43") (name "/~{NRST}2") (class "Default")
      (node (ref "D5") (pin "1") (pinfunction "A_1") (pintype "passive"))
      (node (ref "P7") (pin "1") (pinfunction "1_1") (pintype "passive"))
    )
    (net (code "44") (name "3V3") (class "Default")
      (node (ref "C17") (pin "2") (pinfunction "2_2") (pintype "passive"))
      (node (ref "JP15") (pin "1") (pinfunction "1_1") (pintype "passive"))
      (node (ref "JP15") (pin "2") (pinfunction "2_2") (pintype "passive"))
      (node (ref "JP15") (pin "3") (pinfunction "3_3") (pintype "passive"))
      (node (ref "JP15") (pin "4") (pinfunction "4_4") (pintype "passive"))
      (node (ref "JP18") (pin "1") (pinfunction "1_1") (pintype "passive"))
      (node (ref "JP4") (pin "1") (pinfunction "1_1") (pintype "passive"))
      (node (ref "JP5") (pin "2") (pinfunction "2_2") (pintype "passive"))
      (node (ref "Q3") (pin "4") (pinfunction "E_4") (pintype "passive"))
      (node (ref "Q5") (pin "2") (pinfunction "E_2") (pintype "passive"))
      (node (ref "R22") (pin "1") (pinfunction "1_1") (pintype "passive"))
      (node (ref "R32") (pin "1") (pinfunction "1_1") (pintype "passive"))
      (node (ref "U4") (pin "1") (pinfunction "VIO_1") (pintype "passive"))
    )
    (net (code "45") (name "GND") (class "Default")
      (node (ref "C1") (pin "2") (pinfunction "2_2") (pintype "passive"))
      (node (ref "C10") (pin "2") (pinfunction "2_2") (pintype "passive"))
      (node (ref "C12") (pin "2") (pinfunction "2_2") (pintype "passive"))
      (node (ref "C13") (pin "1") (pinfunction "1_1") (pintype "passive"))
      (node (ref "C14") (pin "2") (pinfunction "2_2") (pintype "passive"))
      (node (ref "C15") (pin "1") (pinfunction "1_1") (pintype "passive"))
      (node (ref "C16") (pin "2") (pinfunction "2_2") (pintype "passive"))
      (node (ref "C17") (pin "1") (pinfunction "1_1") (pintype "passive"))
      (node (ref "C18") (pin "1") (pinfunction "1_1") (pintype "passive"))
      (node (ref "C19") (pin "1") (pinfunction "1_1") (pintype "passive"))
      (node (ref "C2") (pin "2") (pinfunction "2_2") (pintype "passive"))
      (node (ref "C20") (pin "1") (pinfunction "1_1") (pintype "passive"))
      (node (ref "C3") (pin "1") (pinfunction "1_1") (pintype "passive"))
      (node (ref "C4") (pin "2") (pinfunction "2_2") (pintype "passive"))
      (node (ref "C5") (pin "2") (pinfunction "2_2") (pintype "passive"))
      (node (ref "C7") (pin "2") (pinfunction "2_2") (pintype "passive"))
      (node (ref "C8") (pin "2") (pinfunction "2_2") (pintype "passive"))
      (node (ref "C9") (pin "2") (pinfunction "2_2") (pintype "passive"))
      (node (ref "D2") (pin "3") (pinfunction "GND_3") (pintype "passive"))
      (node (ref "D2") (pin "8") (pinfunction "GND_8") (pintype "passive"))
      (node (ref "D4") (pin "3") (pinfunction "GND_3") (pintype "passive"))
      (node (ref "D4") (pin "8") (pinfunction "GND_8") (pintype "passive"))
      (node (ref "JP10") (pin "3") (pinfunction "3_3") (pintype "passive"))
      (node (ref "JP11") (pin "1") (pinfunction "1_1") (pintype "passive"))
      (node (ref "JP11") (pin "2") (pinfunction "2_2") (pintype "passive"))
      (node (ref "JP12") (pin "1") (pinfunction "1_1") (pintype "passive"))
      (node (ref "JP16") (pin "1") (pinfunction "1_1") (pintype "passive"))
      (node (ref "JP16") (pin "2") (pinfunction "2_2") (pintype "passive"))
      (node (ref "JP16") (pin "3") (pinfunction "3_3") (pintype "passive"))
      (node (ref "JP16") (pin "4") (pinfunction "4_4") (pintype "passive"))
      (node (ref "JP20") (pin "2") (pinfunction "2_2") (pintype "passive"))
      (node (ref "JP21") (pin "2") (pinfunction "2_2") (pintype "passive"))
      (node (ref "JP6") (pin "3") (pinfunction "3_3") (pintype "passive"))
      (node (ref "JP7") (pin "1") (pinfunction "1_1") (pintype "passive"))
      (node (ref "JP7") (pin "2") (pinfunction "2_2") (pintype "passive"))
      (node (ref "JP8") (pin "3") (pinfunction "3_3") (pintype "passive"))
      (node (ref "Q2") (pin "2") (pinfunction "S_2") (pintype "passive"))
      (node (ref "R1") (pin "1") (pinfunction "1_1") (pintype "passive"))
      (node (ref "R11") (pin "1") (pinfunction "1_1") (pintype "passive"))
      (node (ref "R13") (pin "1") (pinfunction "1_1") (pintype "passive"))
      (node (ref "R18") (pin "1") (pinfunction "1_1") (pintype "passive"))
      (node (ref "R20") (pin "1") (pinfunction "1_1") (pintype "passive"))
      (node (ref "R23") (pin "2") (pinfunction "2_2") (pintype "passive"))
      (node (ref "R24") (pin "1") (pinfunction "1_1") (pintype "passive"))
      (node (ref "R30") (pin "2") (pinfunction "2_2") (pintype "passive"))
      (node (ref "R31") (pin "1") (pinfunction "1_1") (pintype "passive"))
      (node (ref "R8") (pin "2") (pinfunction "2_2") (pintype "passive"))
      (node (ref "U1") (pin "11") (pinfunction "TP_11") (pintype "passive"))
      (node (ref "U1") (pin "3") (pinfunction "GNDA_3") (pintype "passive"))
      (node (ref "U1") (pin "9") (pinfunction "GND_9") (pintype "passive"))
      (node (ref "U2") (pin "2") (pinfunction "VSS_2") (pintype "power_in"))
      (node (ref "U3") (pin "2") (pinfunction "GND_2") (pintype "passive"))
      (node (ref "U4") (pin "17") (pinfunction "TP_17") (pintype "passive"))
      (node (ref "U4") (pin "2") (pinfunction "GND_2") (pintype "passive"))
      (node (ref "U5") (pin "1") (pinfunction "GND_1") (pintype "passive"))
      (node (ref "USB1") (pin "1") (pinfunction "SH1_1") (pintype "passive"))
      (node (ref "USB1") (pin "2") (pinfunction "SH2_2") (pintype "passive"))
      (node (ref "USB1") (pin "3") (pinfunction "SH3_3") (pintype "passive"))
      (node (ref "USB1") (pin "4") (pinfunction "SH4_4") (pintype "passive"))
      (node (ref "USB1") (pin "A1") (pinfunction "GND_A1") (pintype "passive"))
      (node (ref "USB1") (pin "A12") (pinfunction "GND_A12") (pintype "passive"))
      (node (ref "USB1") (pin "B1") (pinfunction "GND_B1") (pintype "passive"))
      (node (ref "USB1") (pin "B12") (pinfunction "GND_B12") (pintype "passive"))
      (node (ref "USB2") (pin "1") (pinfunction "SH1_1") (pintype "passive"))
      (node (ref "USB2") (pin "2") (pinfunction "SH2_2") (pintype "passive"))
      (node (ref "USB2") (pin "3") (pinfunction "SH3_3") (pintype "passive"))
      (node (ref "USB2") (pin "4") (pinfunction "SH4_4") (pintype "passive"))
      (node (ref "USB2") (pin "A1") (pinfunction "GND_A1") (pintype "passive"))
      (node (ref "USB2") (pin "A12") (pinfunction "GND_A12") (pintype "passive"))
      (node (ref "USB2") (pin "B1") (pinfunction "GND_B1") (pintype "passive"))
      (node (ref "USB2") (pin "B12") (pinfunction "GND_B12") (pintype "passive"))
      (node (ref "X1") (pin "2") (pinfunction "GND_2") (pintype "passive"))
      (node (ref "X1") (pin "4") (pinfunction "GND_4") (pintype "passive"))
    )
    (net (code "46") (name "Net-(C3-Pad2)") (class "Default")
      (node (ref "C3") (pin "2") (pinfunction "2_2") (pintype "passive"))
      (node (ref "JP4") (pin "3") (pinfunction "3_3") (pintype "passive"))
      (node (ref "L2") (pin "1") (pinfunction "1_1") (pintype "passive"))
    )
    (net (code "47") (name "Net-(C4-Pad1)") (class "Default")
      (node (ref "C4") (pin "1") (pinfunction "1_1") (pintype "passive"))
      (node (ref "JP5") (pin "1") (pinfunction "1_1") (pintype "passive"))
      (node (ref "L2") (pin "2") (pinfunction "2_2") (pintype "passive"))
      (node (ref "R7") (pin "2") (pinfunction "2_2") (pintype "passive"))
    )
    (net (code "48") (name "Net-(C6-Pad2)") (class "Default")
      (node (ref "C6") (pin "2") (pinfunction "2_2") (pintype "passive"))
      (node (ref "JP8") (pin "1") (pinfunction "1_1") (pintype "passive"))
      (node (ref "JP8") (pin "2") (pinfunction "2_2") (pintype "passive"))
      (node (ref "R9") (pin "1") (pinfunction "1_1") (pintype "passive"))
    )
    (net (code "49") (name "Net-(C7-Pad1)") (class "Default")
      (node (ref "C7") (pin "1") (pinfunction "1_1") (pintype "passive"))
      (node (ref "R7") (pin "1") (pinfunction "1_1") (pintype "passive"))
    )
    (net (code "50") (name "Net-(D1-A)") (class "Default")
      (node (ref "D1") (pin "1") (pinfunction "A_1") (pintype "passive"))
      (node (ref "P1") (pin "1") (pinfunction "1_1") (pintype "passive"))
      (node (ref "SW1") (pin "1") (pinfunction "1_1") (pintype "passive"))
      (node (ref "SW1") (pin "2") (pinfunction "2_2") (pintype "passive"))
    )
    (net (code "51") (name "Net-(D1-C)") (class "Default")
      (node (ref "D1") (pin "2") (pinfunction "C_2") (pintype "passive"))
      (node (ref "JP9") (pin "1") (pinfunction "1_1") (pintype "passive"))
    )
    (net (code "52") (name "Net-(D3-C)") (class "Default")
      (node (ref "D3") (pin "2") (pinfunction "C_2") (pintype "passive"))
      (node (ref "Q3") (pin "6") (pinfunction "C_6") (pintype "passive"))
      (node (ref "R22") (pin "2") (pinfunction "2_2") (pintype "passive"))
    )
    (net (code "53") (name "Net-(D5-C)") (class "Default")
      (node (ref "D5") (pin "2") (pinfunction "C_2") (pintype "passive"))
      (node (ref "Q4") (pin "3") (pinfunction "C_3") (pintype "passive"))
      (node (ref "R32") (pin "2") (pinfunction "2_2") (pintype "passive"))
    )
    (net (code "54") (name "Net-(JP13-Pad1)") (class "Default")
      (node (ref "JP13") (pin "1") (pinfunction "1_1") (pintype "passive"))
      (node (ref "R14") (pin "2") (pinfunction "2_2") (pintype "passive"))
      (node (ref "R17") (pin "1") (pinfunction "1_1") (pintype "passive"))
    )
    (net (code "55") (name "Net-(JP14-Pad2)") (class "Default")
      (node (ref "JP14") (pin "2") (pinfunction "2_2") (pintype "passive"))
      (node (ref "R15") (pin "1") (pinfunction "1_1") (pintype "passive"))
    )
    (net (code "56") (name "Net-(JP18-Pad2)") (class "Default")
      (node (ref "JP18") (pin "2") (pinfunction "2_2") (pintype "passive"))
      (node (ref "R20") (pin "2") (pinfunction "2_2") (pintype "passive"))
    )
    (net (code "57") (name "Net-(JP19-Pad1)") (class "Default")
      (node (ref "JP19") (pin "1") (pinfunction "1_1") (pintype "passive"))
      (node (ref "R17") (pin "2") (pinfunction "2_2") (pintype "passive"))
      (node (ref "R19") (pin "2") (pinfunction "2_2") (pintype "passive"))
    )
    (net (code "58") (name "Net-(LED1-K)") (class "Default")
      (node (ref "LED1") (pin "2") (pinfunction "K_2") (pintype "passive"))
      (node (ref "R5") (pin "2") (pinfunction "2_2") (pintype "passive"))
    )
    (net (code "59") (name "Net-(Q1-G)") (class "Default")
      (node (ref "Q1") (pin "1") (pinfunction "G_1") (pintype "passive"))
      (node (ref "Q2") (pin "3") (pinfunction "D_3") (pintype "passive"))
      (node (ref "R6") (pin "1") (pinfunction "1_1") (pintype "passive"))
      (node (ref "VD2") (pin "1") (pinfunction "1_1") (pintype "passive"))
    )
    (net (code "60") (name "Net-(Q2-G)") (class "Default")
      (node (ref "JP10") (pin "2") (pinfunction "2_2") (pintype "passive"))
      (node (ref "JP9") (pin "2") (pinfunction "2_2") (pintype "passive"))
      (node (ref "Q2") (pin "1") (pinfunction "G_1") (pintype "passive"))
      (node (ref "R12") (pin "2") (pinfunction "2_2") (pintype "passive"))
      (node (ref "R13") (pin "2") (pinfunction "2_2") (pintype "passive"))
      (node (ref "R18") (pin "2") (pinfunction "2_2") (pintype "passive"))
      (node (ref "U1") (pin "6") (pinfunction "EN_6") (pintype "input"))
      (node (ref "VD3") (pin "3") (pinfunction "3_3") (pintype "passive"))
    )
    (net (code "61") (name "Net-(Q3-B-Pad2)") (class "Default")
      (node (ref "Q3") (pin "2") (pinfunction "B_2") (pintype "passive"))
      (node (ref "R27") (pin "2") (pinfunction "2_2") (pintype "passive"))
    )
    (net (code "62") (name "Net-(Q3-B-Pad5)") (class "Default")
      (node (ref "Q3") (pin "5") (pinfunction "B_5") (pintype "passive"))
      (node (ref "R25") (pin "1") (pinfunction "1_1") (pintype "passive"))
    )
    (net (code "63") (name "Net-(Q3-C-Pad3)") (class "Default")
      (node (ref "Q3") (pin "3") (pinfunction "C_3") (pintype "passive"))
      (node (ref "R26") (pin "2") (pinfunction "2_2") (pintype "passive"))
    )
    (net (code "64") (name "Net-(Q4-B)") (class "Default")
      (node (ref "Q4") (pin "1") (pinfunction "B_1") (pintype "passive"))
      (node (ref "R33") (pin "1") (pinfunction "1_1") (pintype "passive"))
    )
    (net (code "65") (name "Net-(Q4-E)") (class "Default")
      (node (ref "Q4") (pin "2") (pinfunction "E_2") (pintype "passive"))
      (node (ref "R34") (pin "2") (pinfunction "2_2") (pintype "passive"))
      (node (ref "U5") (pin "14") (pinfunction "RTS_14") (pintype "passive"))
    )
    (net (code "66") (name "Net-(Q5-B)") (class "Default")
      (node (ref "Q5") (pin "1") (pinfunction "B_1") (pintype "passive"))
      (node (ref "R34") (pin "1") (pinfunction "1_1") (pintype "passive"))
    )
    (net (code "67") (name "Net-(Q5-C)") (class "Default")
      (node (ref "Q5") (pin "3") (pinfunction "C_3") (pintype "passive"))
      (node (ref "R35") (pin "1") (pinfunction "1_1") (pintype "passive"))
    )
    (net (code "68") (name "Net-(R15-Pad2)") (class "Default")
      (node (ref "R15") (pin "2") (pinfunction "2_2") (pintype "passive"))
      (node (ref "VD3") (pin "2") (pinfunction "2_2") (pintype "passive"))
    )
    (net (code "69") (name "Net-(R16-Pad2)") (class "Default")
      (node (ref "R16") (pin "2") (pinfunction "2_2") (pintype "passive"))
      (node (ref "VD3") (pin "1") (pinfunction "1_1") (pintype "passive"))
    )
    (net (code "70") (name "Net-(U1-L1)") (class "Default")
      (node (ref "L1") (pin "1") (pintype "passive"))
      (node (ref "U1") (pin "4") (pinfunction "L1_4") (pintype "passive"))
    )
    (net (code "71") (name "Net-(U1-L2)") (class "Default")
      (node (ref "L1") (pin "2") (pinfunction "2_2") (pintype "passive"))
      (node (ref "U1") (pin "2") (pinfunction "L2_2") (pintype "passive"))
    )
    (net (code "72") (name "Net-(U1-PS{slash}SYNC)") (class "Default")
      (node (ref "JP6") (pin "2") (pinfunction "2_2") (pintype "passive"))
      (node (ref "R3") (pin "2") (pinfunction "2_2") (pintype "passive"))
      (node (ref "U1") (pin "7") (pinfunction "PS/SYNC_7") (pintype "input"))
    )
    (net (code "73") (name "Net-(U1-VIN)") (class "Default")
      (node (ref "C8") (pin "1") (pinfunction "1_1") (pintype "passive"))
      (node (ref "JP10") (pin "1") (pinfunction "1_1") (pintype "passive"))
      (node (ref "JP3") (pin "2") (pinfunction "2_2") (pintype "passive"))
      (node (ref "JP6") (pin "1") (pinfunction "1_1") (pintype "passive"))
      (node (ref "R12") (pin "1") (pinfunction "1_1") (pintype "passive"))
      (node (ref "R3") (pin "1") (pinfunction "1_1") (pintype "passive"))
      (node (ref "SW1") (pin "3") (pinfunction "3_3") (pintype "passive"))
      (node (ref "SW1") (pin "4") (pinfunction "4_4") (pintype "passive"))
      (node (ref "U1") (pin "5") (pinfunction "VIN_5") (pintype "passive"))
      (node (ref "U1") (pin "8") (pinfunction "VINA_8") (pintype "passive"))
    )
    (net (code "74") (name "Net-(U2-PROG)") (class "Default")
      (node (ref "R1") (pin "2") (pinfunction "2_2") (pintype "passive"))
      (node (ref "U2") (pin "5") (pinfunction "PROG_5") (pintype "passive"))
    )
    (net (code "75") (name "Net-(U3-IN+)") (class "Default")
      (node (ref "C11") (pin "1") (pinfunction "1_1") (pintype "passive"))
      (node (ref "R19") (pin "1") (pinfunction "1_1") (pintype "passive"))
      (node (ref "U3") (pin "3") (pinfunction "IN+_3") (pintype "power_in"))
    )
    (net (code "76") (name "Net-(U3-IN-)") (class "Default")
      (node (ref "C11") (pin "2") (pinfunction "2_2") (pintype "passive"))
      (node (ref "R14") (pin "1") (pinfunction "1_1") (pintype "passive"))
      (node (ref "U3") (pin "4") (pinfunction "IN-_4") (pintype "passive"))
    )
    (net (code "77") (name "Net-(U3-OUT)") (class "Default")
      (node (ref "C12") (pin "1") (pinfunction "1_1") (pintype "passive"))
      (node (ref "R21") (pin "2") (pinfunction "2_2") (pintype "passive"))
      (node (ref "U3") (pin "1") (pinfunction "OUT_1") (pintype "passive"))
    )
    (net (code "78") (name "Net-(U4-DTR)") (class "Default")
      (node (ref "R27") (pin "1") (pinfunction "1_1") (pintype "passive"))
      (node (ref "U4") (pin "12") (pinfunction "DTR_12") (pintype "passive"))
    )
    (net (code "79") (name "Net-(U4-RTS)") (class "Default")
      (node (ref "Q3") (pin "1") (pinfunction "E_1") (pintype "passive"))
      (node (ref "R25") (pin "2") (pinfunction "2_2") (pintype "passive"))
      (node (ref "U4") (pin "13") (pinfunction "RTS_13") (pintype "passive"))
    )
    (net (code "80") (name "Net-(U4-V3)") (class "Default")
      (node (ref "C14") (pin "1") (pinfunction "1_1") (pintype "passive"))
      (node (ref "U4") (pin "6") (pinfunction "V3_6") (pintype "passive"))
    )
    (net (code "81") (name "Net-(U5-DTR)") (class "Default")
      (node (ref "R33") (pin "2") (pinfunction "2_2") (pintype "passive"))
      (node (ref "U5") (pin "13") (pinfunction "DTR_13") (pintype "passive"))
    )
    (net (code "82") (name "Net-(U5-V3)") (class "Default")
      (node (ref "C16") (pin "1") (pinfunction "1_1") (pintype "passive"))
      (node (ref "U5") (pin "4") (pinfunction "V3_4") (pintype "passive"))
    )
    (net (code "83") (name "Net-(U5-XI)") (class "Default")
      (node (ref "C20") (pin "2") (pinfunction "2_2") (pintype "passive"))
      (node (ref "U5") (pin "7") (pinfunction "XI_7") (pintype "passive"))
      (node (ref "X1") (pin "3") (pinfunction "3_3") (pintype "passive"))
    )
    (net (code "84") (name "Net-(U5-XO)") (class "Default")
      (node (ref "C19") (pin "2") (pinfunction "2_2") (pintype "passive"))
      (node (ref "U5") (pin "8") (pinfunction "XO_8") (pintype "passive"))
      (node (ref "X1") (pin "1") (pinfunction "1_1") (pintype "passive"))
    )
    (net (code "85") (name "unconnected-(U4-ACT#-Pad10)") (class "Default")
      (node (ref "U4") (pin "10") (pinfunction "ACT#_10") (pintype "passive+no_connect"))
    )
    (net (code "86") (name "unconnected-(U4-CTS-Pad15)") (class "Default")
      (node (ref "U4") (pin "15") (pinfunction "CTS_15") (pintype "passive+no_connect"))
    )
    (net (code "87") (name "unconnected-(U4-DCD-Pad11)") (class "Default")
      (node (ref "U4") (pin "11") (pinfunction "DCD_11") (pintype "passive+no_connect"))
    )
    (net (code "88") (name "unconnected-(U4-DSR-Pad14)") (class "Default")
      (node (ref "U4") (pin "14") (pinfunction "DSR_14") (pintype "passive+no_connect"))
    )
    (net (code "89") (name "unconnected-(U4-RI-Pad16)") (class "Default")
      (node (ref "U4") (pin "16") (pinfunction "RI_16") (pintype "passive+no_connect"))
    )
    (net (code "90") (name "unconnected-(U5-CTS-Pad9)") (class "Default")
      (node (ref "U5") (pin "9") (pinfunction "CTS_9") (pintype "passive+no_connect"))
    )
    (net (code "91") (name "unconnected-(U5-DCD-Pad12)") (class "Default")
      (node (ref "U5") (pin "12") (pinfunction "DCD_12") (pintype "passive+no_connect"))
    )
    (net (code "92") (name "unconnected-(U5-DSR-Pad10)") (class "Default")
      (node (ref "U5") (pin "10") (pinfunction "DSR_10") (pintype "passive+no_connect"))
    )
    (net (code "93") (name "unconnected-(U5-RI-Pad11)") (class "Default")
      (node (ref "U5") (pin "11") (pinfunction "RI_11") (pintype "passive+no_connect"))
    )
    (net (code "94") (name "unconnected-(U5-RS232-Pad15)") (class "Default")
      (node (ref "U5") (pin "15") (pinfunction "RS232_15") (pintype "passive+no_connect"))
    )
    (net (code "95") (name "unconnected-(USB1-SBU1-PadA8)") (class "Default")
      (node (ref "USB1") (pin "A8") (pinfunction "SBU1_A8") (pintype "passive+no_connect"))
    )
    (net (code "96") (name "unconnected-(USB1-SBU2-PadB8)") (class "Default")
      (node (ref "USB1") (pin "B8") (pinfunction "SBU2_B8") (pintype "passive+no_connect"))
    )
    (net (code "97") (name "unconnected-(USB2-SBU1-PadA8)") (class "Default")
      (node (ref "USB2") (pin "A8") (pinfunction "SBU1_A8") (pintype "passive+no_connect"))
    )
    (net (code "98") (name "unconnected-(USB2-SBU2-PadB8)") (class "Default")
      (node (ref "USB2") (pin "B8") (pinfunction "SBU2_B8") (pintype "passive+no_connect"))
    )
    (net (code "99") (name "unconnected-(VD1-Pad3)") (class "Default")
      (node (ref "VD1") (pin "3") (pinfunction "3_3") (pintype "passive"))
    )
  )
)
